# FAR.net
KiCad netlist of a schematic drawn in Altium Designer
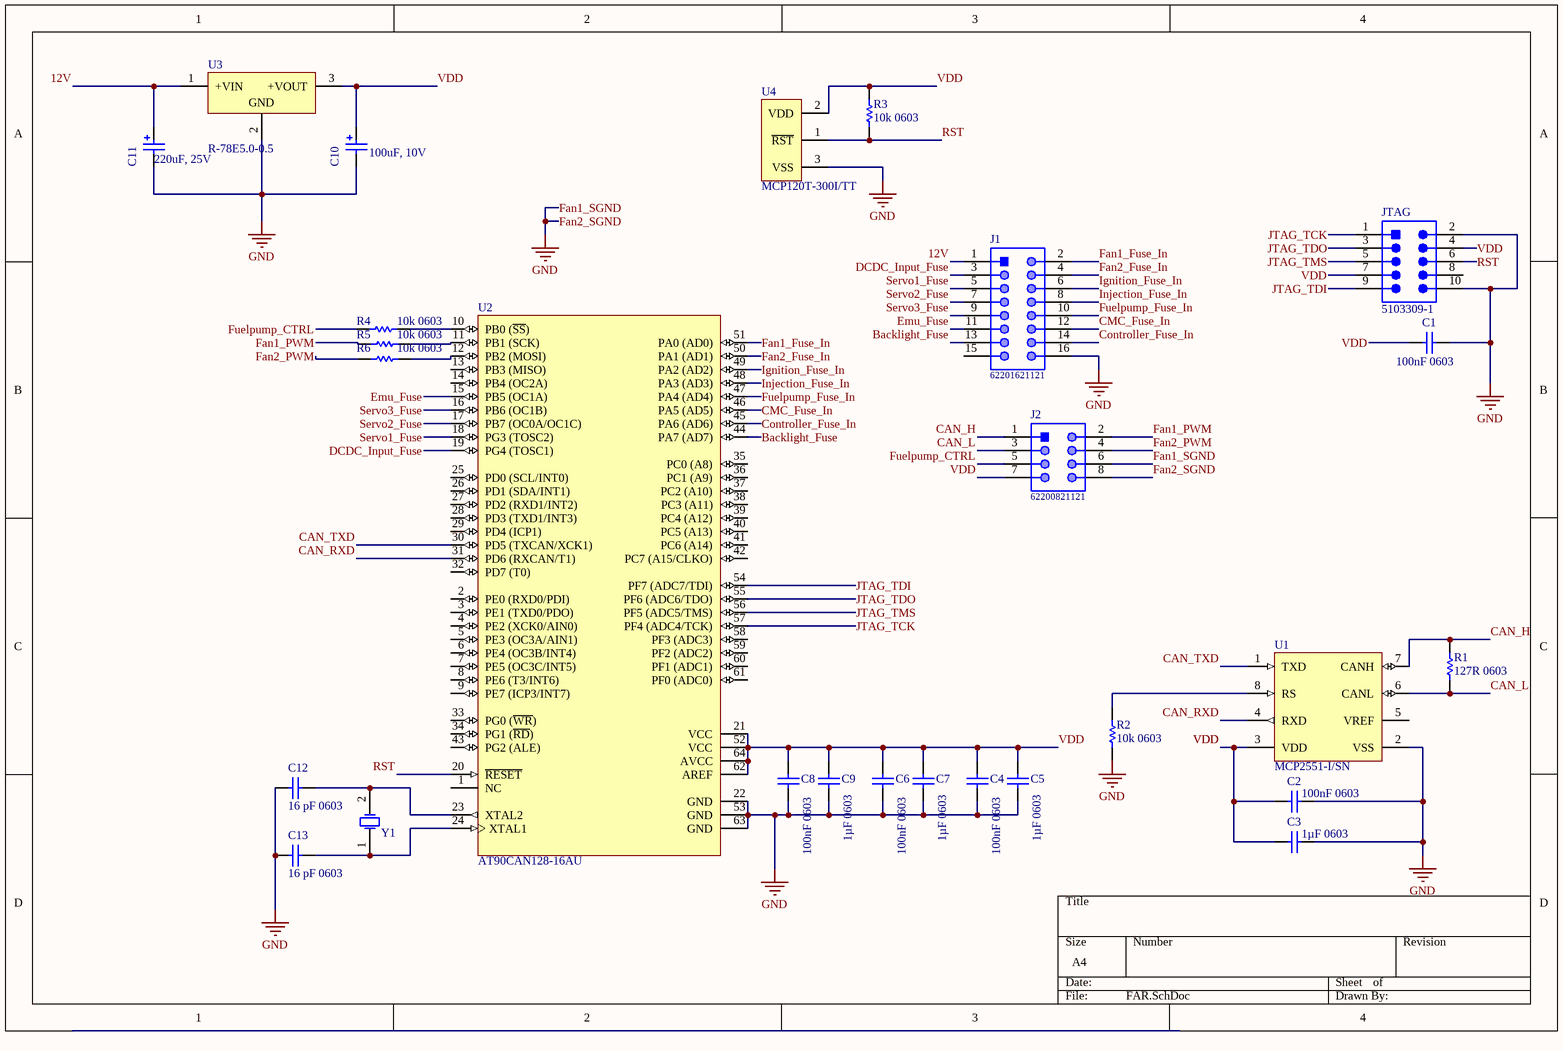
[diagram p0: FAR.SchDoc]

(export (version "E")
  (design (tool "Eeschema 10.0.6"))
  (components
    (comp (ref "C1")
      (value "100nF 0603")
      (footprint "CAPC0603(1608)100_L")
      (description "CAP 100nF 10V ±5% 0603 (1608 Metric) Thickness 1mm SMD")
      (fields (field (name "TOLERANCE") "Â±5%"))
      (libsource (lib "Altium Content Vault") (part "CAP"))
    )
    (comp (ref "C2")
      (value "100nF 0603")
      (footprint "CAPC0603(1608)100_L")
      (description "CAP 100nF 10V ±5% 0603 (1608 Metric) Thickness 1mm SMD")
      (fields (field (name "TOLERANCE") "Â±5%"))
      (libsource (lib "Altium Content Vault") (part "CAP"))
    )
    (comp (ref "C3")
      (value "1µF 0603")
      (footprint "CAPC0603(1608)100_L")
      (description "CAP 100nF 10V ±5% 0603 (1608 Metric) Thickness 1mm SMD")
      (fields (field (name "TOLERANCE") "Â±5%"))
      (libsource (lib "Altium Content Vault") (part "CAP"))
    )
    (comp (ref "C4")
      (value "100nF 0603")
      (footprint "CAPC0603(1608)100_L")
      (description "CAP 100nF 10V ±5% 0603 (1608 Metric) Thickness 1mm SMD")
      (fields (field (name "TOLERANCE") "Â±5%"))
      (libsource (lib "Altium Content Vault") (part "CAP"))
    )
    (comp (ref "C5")
      (value "1µF 0603")
      (footprint "CAPC0603(1608)100_L")
      (description "CAP 100nF 10V ±5% 0603 (1608 Metric) Thickness 1mm SMD")
      (fields (field (name "TOLERANCE") "Â±5%"))
      (libsource (lib "Altium Content Vault") (part "CAP"))
    )
    (comp (ref "C6")
      (value "100nF 0603")
      (footprint "CAPC0603(1608)100_L")
      (description "CAP 100nF 10V ±5% 0603 (1608 Metric) Thickness 1mm SMD")
      (fields (field (name "TOLERANCE") "Â±5%"))
      (libsource (lib "Altium Content Vault") (part "CAP"))
    )
    (comp (ref "C7")
      (value "1µF 0603")
      (footprint "CAPC0603(1608)100_L")
      (description "CAP 100nF 10V ±5% 0603 (1608 Metric) Thickness 1mm SMD")
      (fields (field (name "TOLERANCE") "Â±5%"))
      (libsource (lib "Altium Content Vault") (part "CAP"))
    )
    (comp (ref "C8")
      (value "100nF 0603")
      (footprint "CAPC0603(1608)100_L")
      (description "CAP 100nF 10V ±5% 0603 (1608 Metric) Thickness 1mm SMD")
      (fields (field (name "TOLERANCE") "Â±5%"))
      (libsource (lib "Altium Content Vault") (part "CAP"))
    )
    (comp (ref "C9")
      (value "1µF 0603")
      (footprint "CAPC0603(1608)100_L")
      (description "CAP 100nF 10V ±5% 0603 (1608 Metric) Thickness 1mm SMD")
      (fields (field (name "TOLERANCE") "Â±5%"))
      (libsource (lib "Altium Content Vault") (part "CAP"))
    )
    (comp (ref "C10")
      (value "100uF, 10V")
      (footprint "WCAP-ASLU_6.3x7.7")
      (description "WCAP-ASLU Aluminium Electrolytic Capacitors, D6.3mm x L7.7mm, 100uF, +/-20%, 10VDC")
      (fields (field (name "PART NUMBER") "865090245005") (field (name "PUBLISHER") "Wurth Elektronik"))
      (libsource (lib "Altium_WCAP-ASLU (rev19a)") (part "865090245005"))
    )
    (comp (ref "C11")
      (value "220uF, 25V")
      (footprint "WCAP-ATET_10x12.5")
      (description "WCAP-ATET THT Aluminum Electrolytic Capacitors, D10mm x L12.5mm, 220uF, +/-20%, 25VDC")
      (fields (field (name "PART NUMBER") "860130475006") (field (name "PUBLISHER") "Wurth Elektronik"))
      (libsource (lib "Altium_WCAP-ATET (rev19a)") (part "860130475006"))
    )
    (comp (ref "C12")
      (value "16 pF 0603")
      (footprint "CAPC0603(1608)100_L")
      (description "CAP 100nF 10V ±5% 0603 (1608 Metric) Thickness 1mm SMD")
      (fields (field (name "TOLERANCE") "Â±5%"))
      (libsource (lib "Altium Content Vault") (part "CAP"))
    )
    (comp (ref "C13")
      (value "16 pF 0603")
      (footprint "CAPC0603(1608)100_L")
      (description "CAP 100nF 10V ±5% 0603 (1608 Metric) Thickness 1mm SMD")
      (fields (field (name "TOLERANCE") "Â±5%"))
      (libsource (lib "Altium Content Vault") (part "CAP"))
    )
    (comp (ref "J1")
      (value "62201621121")
      (footprint "62201621121")
      (description "THT Vertical Pin Header WR-PHD, Pitch 1.27 mm, Dual Row, 16 pins")
      (fields (field (name "MANUFACTURER") "Wurth Elektronik") (field (name "PUBLISHER") "WurthElektronik"))
      (libsource (lib "Altium Content Vault") (part "WE-CN-2P-M-R16"))
    )
    (comp (ref "J2")
      (value "62200821121")
      (footprint "62200821121")
      (description "THT Vertical Pin Header WR-PHD, Pitch 1.27 mm, Dual Row, 8 pins")
      (fields (field (name "MANUFACTURER") "Wurth Elektronik") (field (name "PUBLISHER") "WurthElektronik"))
      (libsource (lib "Altium Content Vault") (part "WE-CN-2P-M-R8"))
    )
    (comp (ref "JTAG")
      (value "5103309-1")
      (footprint "TECO-5103309-1_V")
      (fields (field (name "MANUFACTURER") "TE Connectivity"))
      (libsource (lib "Altium Content Vault") (part "CN-2P-M-R10"))
    )
    (comp (ref "R1")
      (value "127R 0603")
      (footprint "RESC0603(1608)_N")
      (description "127R 0.1W 1% 0603 (1608 Metric)  SMD")
      (fields (field (name "POWER") "0.1 W") (field (name "TOLERANCE") "1 %"))
      (libsource (lib "Altium Content Vault") (part "RES"))
    )
    (comp (ref "R2")
      (value "10k 0603")
      (footprint "RESC0603(1608)_N")
      (description "127R 0.1W 1% 0603 (1608 Metric)  SMD")
      (fields (field (name "POWER") "0.1 W") (field (name "TOLERANCE") "1 %"))
      (libsource (lib "Altium Content Vault") (part "RES"))
    )
    (comp (ref "R3")
      (value "10k 0603")
      (footprint "RESC0603(1608)_N")
      (description "127R 0.1W 1% 0603 (1608 Metric)  SMD")
      (fields (field (name "POWER") "0.1 W") (field (name "TOLERANCE") "1 %"))
      (libsource (lib "Altium Content Vault") (part "RES"))
    )
    (comp (ref "R4")
      (value "10k 0603")
      (footprint "RESC0603(1608)_N")
      (description "127R 0.1W 1% 0603 (1608 Metric)  SMD")
      (fields (field (name "POWER") "0.1 W") (field (name "TOLERANCE") "1 %"))
      (libsource (lib "Altium Content Vault") (part "RES"))
    )
    (comp (ref "R5")
      (value "10k 0603")
      (footprint "RESC0603(1608)_N")
      (description "127R 0.1W 1% 0603 (1608 Metric)  SMD")
      (fields (field (name "POWER") "0.1 W") (field (name "TOLERANCE") "1 %"))
      (libsource (lib "Altium Content Vault") (part "RES"))
    )
    (comp (ref "R6")
      (value "10k 0603")
      (footprint "RESC0603(1608)_N")
      (description "127R 0.1W 1% 0603 (1608 Metric)  SMD")
      (fields (field (name "POWER") "0.1 W") (field (name "TOLERANCE") "1 %"))
      (libsource (lib "Altium Content Vault") (part "RES"))
    )
    (comp (ref "U1")
      (value "MCP2551-I/SN")
      (footprint "MCHP-SN8_V")
      (fields (field (name "MANUFACTURER") "Microchip"))
      (libsource (lib "Altium Content Vault") (part "MCHP-MCP2551-SN8"))
    )
    (comp (ref "U2")
      (value "AT90CAN128-16AU")
      (footprint "64A_M")
      (libsource (lib "Altium Content Vault") (part "MC-8B-AT90CAN32-SQ64"))
    )
    (comp (ref "U3")
      (value "R-78E5.0-0.5")
      (footprint "REPO-R-78E-0.5-3_V")
      (description "DC/DC-Converter, 5 V Single Output, 500 mA, -40 to 85 degC, 3-Pin THD, RoHS, Tube")
      (fields (field (name "MANUFACTURER") "Recom Power"))
      (libsource (lib "Altium Content Vault") (part "REPO-R-78XX-3"))
    )
    (comp (ref "U4")
      (value "MCP120T-300I/TT")
      (footprint "SOT-23-TT3_N")
      (libsource (lib "Altium Content Vault") (part "PM-SCCT-MCP120-3"))
    )
    (comp (ref "Y1")
      (value "16MHz, +/-30ppm, 16pF")
      (footprint "WE-XTAL_HC49/4HSMX")
      (description "WE-XTAL Quartz Crystal, size HC49-4HSMX, 16MHz, +/-30ppm, 16pF")
      (fields (field (name "PART NUMBER") "830003237") (field (name "PUBLISHER") "Wurth Elektronik"))
      (libsource (lib "Altium_WE-XTAL (rev19a)") (part "830003237"))
    )
  )
  (nets
    (net (code "1") (name "/12V") (class "Default")
      (node (ref "C11") (pin "2") (pinfunction "P_2") (pintype "passive"))
      (node (ref "J1") (pin "1") (pinfunction "1_1") (pintype "passive"))
      (node (ref "U3") (pin "1") (pinfunction "+VIN_1") (pintype "power_in"))
    )
    (net (code "2") (name "/Backlight_Fuse") (class "Default")
      (node (ref "J1") (pin "13") (pinfunction "13_13") (pintype "passive"))
      (node (ref "U2") (pin "44") (pinfunction "PA7_(AD7)_44") (pintype "bidirectional"))
    )
    (net (code "3") (name "/CAN_H") (class "Default")
      (node (ref "J2") (pin "1") (pinfunction "1_1") (pintype "passive"))
      (node (ref "R1") (pin "2") (pinfunction "2_2") (pintype "passive"))
      (node (ref "U1") (pin "7") (pinfunction "CANH_7") (pintype "bidirectional"))
    )
    (net (code "4") (name "/CAN_L") (class "Default")
      (node (ref "J2") (pin "3") (pinfunction "3_3") (pintype "passive"))
      (node (ref "R1") (pin "1") (pinfunction "1_1") (pintype "passive"))
      (node (ref "U1") (pin "6") (pinfunction "CANL_6") (pintype "bidirectional"))
    )
    (net (code "5") (name "/CAN_RXD") (class "Default")
      (node (ref "U1") (pin "4") (pinfunction "RXD_4") (pintype "output"))
      (node (ref "U2") (pin "31") (pinfunction "PD6_(RXCAN/T1)_31") (pintype "bidirectional"))
    )
    (net (code "6") (name "/CAN_TXD") (class "Default")
      (node (ref "U1") (pin "1") (pinfunction "TXD_1") (pintype "input"))
      (node (ref "U2") (pin "30") (pinfunction "PD5_(TXCAN/XCK1)_30") (pintype "bidirectional"))
    )
    (net (code "7") (name "/CMC_Fuse_In") (class "Default")
      (node (ref "J1") (pin "12") (pinfunction "12_12") (pintype "passive"))
      (node (ref "U2") (pin "46") (pinfunction "PA5_(AD5)_46") (pintype "bidirectional"))
    )
    (net (code "8") (name "/Controller_Fuse_In") (class "Default")
      (node (ref "J1") (pin "14") (pinfunction "14_14") (pintype "passive"))
      (node (ref "U2") (pin "45") (pinfunction "PA6_(AD6)_45") (pintype "bidirectional"))
    )
    (net (code "9") (name "/DCDC_Input_Fuse") (class "Default")
      (node (ref "J1") (pin "3") (pinfunction "3_3") (pintype "passive"))
      (node (ref "U2") (pin "19") (pinfunction "PG4_(TOSC1)_19") (pintype "bidirectional"))
    )
    (net (code "10") (name "/Emu_Fuse") (class "Default")
      (node (ref "J1") (pin "11") (pinfunction "11_11") (pintype "passive"))
      (node (ref "U2") (pin "15") (pinfunction "PB5_(OC1A)_15") (pintype "bidirectional"))
    )
    (net (code "11") (name "/Fan1_Fuse_In") (class "Default")
      (node (ref "J1") (pin "2") (pinfunction "2_2") (pintype "passive"))
      (node (ref "U2") (pin "51") (pinfunction "PA0_(AD0)_51") (pintype "bidirectional"))
    )
    (net (code "12") (name "/Fan1_PWM") (class "Default")
      (node (ref "J2") (pin "2") (pinfunction "2_2") (pintype "passive"))
      (node (ref "R5") (pin "1") (pinfunction "1_1") (pintype "passive"))
    )
    (net (code "13") (name "/Fan2_Fuse_In") (class "Default")
      (node (ref "J1") (pin "4") (pinfunction "4_4") (pintype "passive"))
      (node (ref "U2") (pin "50") (pinfunction "PA1_(AD1)_50") (pintype "bidirectional"))
    )
    (net (code "14") (name "/Fan2_PWM") (class "Default")
      (node (ref "J2") (pin "4") (pinfunction "4_4") (pintype "passive"))
      (node (ref "R6") (pin "1") (pinfunction "1_1") (pintype "passive"))
    )
    (net (code "15") (name "/Fuelpump_CTRL") (class "Default")
      (node (ref "J2") (pin "5") (pinfunction "5_5") (pintype "passive"))
      (node (ref "R4") (pin "1") (pinfunction "1_1") (pintype "passive"))
    )
    (net (code "16") (name "/Fuelpump_Fuse_In") (class "Default")
      (node (ref "J1") (pin "10") (pinfunction "10_10") (pintype "passive"))
      (node (ref "U2") (pin "47") (pinfunction "PA4_(AD4)_47") (pintype "bidirectional"))
    )
    (net (code "17") (name "/Ignition_Fuse_In") (class "Default")
      (node (ref "J1") (pin "6") (pinfunction "6_6") (pintype "passive"))
      (node (ref "U2") (pin "49") (pinfunction "PA2_(AD2)_49") (pintype "bidirectional"))
    )
    (net (code "18") (name "/Injection_Fuse_In") (class "Default")
      (node (ref "J1") (pin "8") (pinfunction "8_8") (pintype "passive"))
      (node (ref "U2") (pin "48") (pinfunction "PA3_(AD3)_48") (pintype "bidirectional"))
    )
    (net (code "19") (name "/JTAG_TCK") (class "Default")
      (node (ref "JTAG") (pin "1") (pinfunction "1_1") (pintype "passive"))
      (node (ref "U2") (pin "57") (pinfunction "PF4_(ADC4/TCK)_57") (pintype "bidirectional"))
    )
    (net (code "20") (name "/JTAG_TDI") (class "Default")
      (node (ref "JTAG") (pin "9") (pinfunction "9_9") (pintype "passive"))
      (node (ref "U2") (pin "54") (pinfunction "PF7_(ADC7/TDI)_54") (pintype "bidirectional"))
    )
    (net (code "21") (name "/JTAG_TDO") (class "Default")
      (node (ref "JTAG") (pin "3") (pinfunction "3_3") (pintype "passive"))
      (node (ref "U2") (pin "55") (pinfunction "PF6_(ADC6/TDO)_55") (pintype "bidirectional"))
    )
    (net (code "22") (name "/JTAG_TMS") (class "Default")
      (node (ref "JTAG") (pin "5") (pinfunction "5_5") (pintype "passive"))
      (node (ref "U2") (pin "56") (pinfunction "PF5_(ADC5/TMS)_56") (pintype "bidirectional"))
    )
    (net (code "23") (name "/RST") (class "Default")
      (node (ref "JTAG") (pin "6") (pinfunction "6_6") (pintype "passive"))
      (node (ref "R3") (pin "2") (pinfunction "2_2") (pintype "passive"))
      (node (ref "U2") (pin "20") (pinfunction "~{RESET}_20") (pintype "input"))
      (node (ref "U4") (pin "1") (pinfunction "~{RST}_1") (pintype "open_collector"))
    )
    (net (code "24") (name "/Servo1_Fuse") (class "Default")
      (node (ref "J1") (pin "5") (pinfunction "5_5") (pintype "passive"))
      (node (ref "U2") (pin "18") (pinfunction "PG3_(TOSC2)_18") (pintype "bidirectional"))
    )
    (net (code "25") (name "/Servo2_Fuse") (class "Default")
      (node (ref "J1") (pin "7") (pinfunction "7_7") (pintype "passive"))
      (node (ref "U2") (pin "17") (pinfunction "PB7_(OC0A/OC1C)_17") (pintype "bidirectional"))
    )
    (net (code "26") (name "/Servo3_Fuse") (class "Default")
      (node (ref "J1") (pin "9") (pinfunction "9_9") (pintype "passive"))
      (node (ref "U2") (pin "16") (pinfunction "PB6_(OC1B)_16") (pintype "bidirectional"))
    )
    (net (code "27") (name "/VDD") (class "Default")
      (node (ref "C1") (pin "1") (pinfunction "1_1") (pintype "passive"))
      (node (ref "C10") (pin "2") (pinfunction "P_2") (pintype "passive"))
      (node (ref "C2") (pin "1") (pinfunction "1_1") (pintype "passive"))
      (node (ref "C3") (pin "1") (pinfunction "1_1") (pintype "passive"))
      (node (ref "C4") (pin "2") (pinfunction "2_2") (pintype "passive"))
      (node (ref "C5") (pin "2") (pinfunction "2_2") (pintype "passive"))
      (node (ref "C6") (pin "2") (pinfunction "2_2") (pintype "passive"))
      (node (ref "C7") (pin "2") (pinfunction "2_2") (pintype "passive"))
      (node (ref "C8") (pin "2") (pinfunction "2_2") (pintype "passive"))
      (node (ref "C9") (pin "2") (pinfunction "2_2") (pintype "passive"))
      (node (ref "J2") (pin "7") (pinfunction "7_7") (pintype "passive"))
      (node (ref "JTAG") (pin "4") (pinfunction "4_4") (pintype "passive"))
      (node (ref "JTAG") (pin "7") (pinfunction "7_7") (pintype "passive"))
      (node (ref "R3") (pin "1") (pinfunction "1_1") (pintype "passive"))
      (node (ref "U1") (pin "3") (pinfunction "VDD_3") (pintype "power_in"))
      (node (ref "U2") (pin "21") (pinfunction "VCC_21") (pintype "power_in"))
      (node (ref "U2") (pin "52") (pinfunction "VCC_52") (pintype "power_in"))
      (node (ref "U2") (pin "62") (pinfunction "AREF_62") (pintype "power_in"))
      (node (ref "U2") (pin "64") (pinfunction "AVCC_64") (pintype "power_in"))
      (node (ref "U3") (pin "3") (pinfunction "+VOUT_3") (pintype "power_in"))
      (node (ref "U4") (pin "2") (pinfunction "VDD_2") (pintype "power_in"))
    )
    (net (code "28") (name "GND") (class "Default")
      (node (ref "C1") (pin "2") (pinfunction "2_2") (pintype "passive"))
      (node (ref "C10") (pin "1") (pinfunction "N_1") (pintype "passive"))
      (node (ref "C11") (pin "1") (pinfunction "N_1") (pintype "passive"))
      (node (ref "C12") (pin "2") (pinfunction "2_2") (pintype "passive"))
      (node (ref "C13") (pin "2") (pinfunction "2_2") (pintype "passive"))
      (node (ref "C2") (pin "2") (pinfunction "2_2") (pintype "passive"))
      (node (ref "C3") (pin "2") (pinfunction "2_2") (pintype "passive"))
      (node (ref "C4") (pin "1") (pinfunction "1_1") (pintype "passive"))
      (node (ref "C5") (pin "1") (pinfunction "1_1") (pintype "passive"))
      (node (ref "C6") (pin "1") (pinfunction "1_1") (pintype "passive"))
      (node (ref "C7") (pin "1") (pinfunction "1_1") (pintype "passive"))
      (node (ref "C8") (pin "1") (pinfunction "1_1") (pintype "passive"))
      (node (ref "C9") (pin "1") (pinfunction "1_1") (pintype "passive"))
      (node (ref "J1") (pin "16") (pinfunction "16_16") (pintype "passive"))
      (node (ref "J2") (pin "6") (pinfunction "6_6") (pintype "passive"))
      (node (ref "J2") (pin "8") (pinfunction "8_8") (pintype "passive"))
      (node (ref "JTAG") (pin "10") (pinfunction "10_10") (pintype "passive"))
      (node (ref "JTAG") (pin "2") (pinfunction "2_2") (pintype "passive"))
      (node (ref "R2") (pin "1") (pinfunction "1_1") (pintype "passive"))
      (node (ref "U1") (pin "2") (pinfunction "VSS_2") (pintype "power_in"))
      (node (ref "U2") (pin "22") (pinfunction "GND_22") (pintype "power_in"))
      (node (ref "U2") (pin "53") (pinfunction "GND_53") (pintype "power_in"))
      (node (ref "U2") (pin "63") (pinfunction "GND_63") (pintype "power_in"))
      (node (ref "U3") (pin "2") (pinfunction "GND_2") (pintype "power_in"))
      (node (ref "U4") (pin "3") (pinfunction "VSS_3") (pintype "power_in"))
    )
    (net (code "29") (name "Net-(U1-RS)") (class "Default")
      (node (ref "R2") (pin "2") (pinfunction "2_2") (pintype "passive"))
      (node (ref "U1") (pin "8") (pinfunction "RS_8") (pintype "input"))
    )
    (net (code "30") (name "Net-(U2-PB0_(~{SS}))") (class "Default")
      (node (ref "R4") (pin "2") (pinfunction "2_2") (pintype "passive"))
      (node (ref "U2") (pin "10") (pinfunction "PB0_(~{SS})_10") (pintype "bidirectional"))
    )
    (net (code "31") (name "Net-(U2-PB1_(SCK))") (class "Default")
      (node (ref "R5") (pin "2") (pinfunction "2_2") (pintype "passive"))
      (node (ref "U2") (pin "11") (pinfunction "PB1_(SCK)_11") (pintype "bidirectional"))
    )
    (net (code "32") (name "Net-(U2-PB2_(MOSI))") (class "Default")
      (node (ref "R6") (pin "2") (pinfunction "2_2") (pintype "passive"))
      (node (ref "U2") (pin "12") (pinfunction "PB2_(MOSI)_12") (pintype "bidirectional"))
    )
    (net (code "33") (name "Net-(U2-XTAL1)") (class "Default")
      (node (ref "C13") (pin "1") (pinfunction "1_1") (pintype "passive"))
      (node (ref "U2") (pin "24") (pinfunction "XTAL1_24") (pintype "input"))
      (node (ref "Y1") (pin "1") (pinfunction "OSC1_1") (pintype "passive"))
    )
    (net (code "34") (name "Net-(U2-XTAL2)") (class "Default")
      (node (ref "C12") (pin "1") (pinfunction "1_1") (pintype "passive"))
      (node (ref "U2") (pin "23") (pinfunction "XTAL2_23") (pintype "output"))
      (node (ref "Y1") (pin "2") (pinfunction "OSC2_2") (pintype "passive"))
    )
    (net (code "35") (name "unconnected-(J1-Pad15)") (class "Default")
      (node (ref "J1") (pin "15") (pinfunction "15_15") (pintype "passive"))
    )
    (net (code "36") (name "unconnected-(JTAG-Pad8)") (class "Default")
      (node (ref "JTAG") (pin "8") (pinfunction "8_8") (pintype "passive"))
    )
    (net (code "37") (name "unconnected-(U1-VREF-Pad5)") (class "Default")
      (node (ref "U1") (pin "5") (pinfunction "VREF_5") (pintype "power_in"))
    )
    (net (code "38") (name "unconnected-(U2-NC-Pad1)") (class "Default")
      (node (ref "U2") (pin "1") (pinfunction "NC_1") (pintype "passive"))
    )
    (net (code "39") (name "unconnected-(U2-PB3_(MISO)-Pad13)") (class "Default")
      (node (ref "U2") (pin "13") (pinfunction "PB3_(MISO)_13") (pintype "bidirectional"))
    )
    (net (code "40") (name "unconnected-(U2-PB4_(OC2A)-Pad14)") (class "Default")
      (node (ref "U2") (pin "14") (pinfunction "PB4_(OC2A)_14") (pintype "bidirectional"))
    )
    (net (code "41") (name "unconnected-(U2-PC0_(A8)-Pad35)") (class "Default")
      (node (ref "U2") (pin "35") (pinfunction "PC0_(A8)_35") (pintype "bidirectional"))
    )
    (net (code "42") (name "unconnected-(U2-PC1_(A9)-Pad36)") (class "Default")
      (node (ref "U2") (pin "36") (pinfunction "PC1_(A9)_36") (pintype "bidirectional"))
    )
    (net (code "43") (name "unconnected-(U2-PC2_(A10)-Pad37)") (class "Default")
      (node (ref "U2") (pin "37") (pinfunction "PC2_(A10)_37") (pintype "bidirectional"))
    )
    (net (code "44") (name "unconnected-(U2-PC3_(A11)-Pad38)") (class "Default")
      (node (ref "U2") (pin "38") (pinfunction "PC3_(A11)_38") (pintype "bidirectional"))
    )
    (net (code "45") (name "unconnected-(U2-PC4_(A12)-Pad39)") (class "Default")
      (node (ref "U2") (pin "39") (pinfunction "PC4_(A12)_39") (pintype "bidirectional"))
    )
    (net (code "46") (name "unconnected-(U2-PC5_(A13)-Pad40)") (class "Default")
      (node (ref "U2") (pin "40") (pinfunction "PC5_(A13)_40") (pintype "bidirectional"))
    )
    (net (code "47") (name "unconnected-(U2-PC6_(A14)-Pad41)") (class "Default")
      (node (ref "U2") (pin "41") (pinfunction "PC6_(A14)_41") (pintype "bidirectional"))
    )
    (net (code "48") (name "unconnected-(U2-PC7_(A15{slash}CLKO)-Pad42)") (class "Default")
      (node (ref "U2") (pin "42") (pinfunction "PC7_(A15/CLKO)_42") (pintype "bidirectional"))
    )
    (net (code "49") (name "unconnected-(U2-PD0_(SCL{slash}INT0)-Pad25)") (class "Default")
      (node (ref "U2") (pin "25") (pinfunction "PD0_(SCL/INT0)_25") (pintype "bidirectional"))
    )
    (net (code "50") (name "unconnected-(U2-PD1_(SDA{slash}INT1)-Pad26)") (class "Default")
      (node (ref "U2") (pin "26") (pinfunction "PD1_(SDA/INT1)_26") (pintype "bidirectional"))
    )
    (net (code "51") (name "unconnected-(U2-PD2_(RXD1{slash}INT2)-Pad27)") (class "Default")
      (node (ref "U2") (pin "27") (pinfunction "PD2_(RXD1/INT2)_27") (pintype "bidirectional"))
    )
    (net (code "52") (name "unconnected-(U2-PD3_(TXD1{slash}INT3)-Pad28)") (class "Default")
      (node (ref "U2") (pin "28") (pinfunction "PD3_(TXD1/INT3)_28") (pintype "bidirectional"))
    )
    (net (code "53") (name "unconnected-(U2-PD4_(ICP1)-Pad29)") (class "Default")
      (node (ref "U2") (pin "29") (pinfunction "PD4_(ICP1)_29") (pintype "bidirectional"))
    )
    (net (code "54") (name "unconnected-(U2-PD7_(T0)-Pad32)") (class "Default")
      (node (ref "U2") (pin "32") (pinfunction "PD7_(T0)_32") (pintype "bidirectional"))
    )
    (net (code "55") (name "unconnected-(U2-PE0_(RXD0{slash}PDI)-Pad2)") (class "Default")
      (node (ref "U2") (pin "2") (pinfunction "PE0_(RXD0/PDI)_2") (pintype "bidirectional"))
    )
    (net (code "56") (name "unconnected-(U2-PE1_(TXD0{slash}PDO)-Pad3)") (class "Default")
      (node (ref "U2") (pin "3") (pinfunction "PE1_(TXD0/PDO)_3") (pintype "bidirectional"))
    )
    (net (code "57") (name "unconnected-(U2-PE2_(XCK0{slash}AIN0)-Pad4)") (class "Default")
      (node (ref "U2") (pin "4") (pinfunction "PE2_(XCK0/AIN0)_4") (pintype "bidirectional"))
    )
    (net (code "58") (name "unconnected-(U2-PE3_(OC3A{slash}AIN1)-Pad5)") (class "Default")
      (node (ref "U2") (pin "5") (pinfunction "PE3_(OC3A/AIN1)_5") (pintype "bidirectional"))
    )
    (net (code "59") (name "unconnected-(U2-PE4_(OC3B{slash}INT4)-Pad6)") (class "Default")
      (node (ref "U2") (pin "6") (pinfunction "PE4_(OC3B/INT4)_6") (pintype "bidirectional"))
    )
    (net (code "60") (name "unconnected-(U2-PE5_(OC3C{slash}INT5)-Pad7)") (class "Default")
      (node (ref "U2") (pin "7") (pinfunction "PE5_(OC3C/INT5)_7") (pintype "bidirectional"))
    )
    (net (code "61") (name "unconnected-(U2-PE6_(T3{slash}INT6)-Pad8)") (class "Default")
      (node (ref "U2") (pin "8") (pinfunction "PE6_(T3/INT6)_8") (pintype "bidirectional"))
    )
    (net (code "62") (name "unconnected-(U2-PE7_(ICP3{slash}INT7)-Pad9)") (class "Default")
      (node (ref "U2") (pin "9") (pinfunction "PE7_(ICP3/INT7)_9") (pintype "bidirectional"))
    )
    (net (code "63") (name "unconnected-(U2-PF0_(ADC0)-Pad61)") (class "Default")
      (node (ref "U2") (pin "61") (pinfunction "PF0_(ADC0)_61") (pintype "bidirectional"))
    )
    (net (code "64") (name "unconnected-(U2-PF1_(ADC1)-Pad60)") (class "Default")
      (node (ref "U2") (pin "60") (pinfunction "PF1_(ADC1)_60") (pintype "bidirectional"))
    )
    (net (code "65") (name "unconnected-(U2-PF2_(ADC2)-Pad59)") (class "Default")
      (node (ref "U2") (pin "59") (pinfunction "PF2_(ADC2)_59") (pintype "bidirectional"))
    )
    (net (code "66") (name "unconnected-(U2-PF3_(ADC3)-Pad58)") (class "Default")
      (node (ref "U2") (pin "58") (pinfunction "PF3_(ADC3)_58") (pintype "bidirectional"))
    )
    (net (code "67") (name "unconnected-(U2-PG0_(~{WR})-Pad33)") (class "Default")
      (node (ref "U2") (pin "33") (pinfunction "PG0_(~{WR})_33") (pintype "bidirectional"))
    )
    (net (code "68") (name "unconnected-(U2-PG1_(~{RD})-Pad34)") (class "Default")
      (node (ref "U2") (pin "34") (pinfunction "PG1_(~{RD})_34") (pintype "bidirectional"))
    )
    (net (code "69") (name "unconnected-(U2-PG2_(ALE)-Pad43)") (class "Default")
      (node (ref "U2") (pin "43") (pinfunction "PG2_(ALE)_43") (pintype "bidirectional"))
    )
  )
)
